# HighRangeAccelerometer.net
KiCad netlist of a schematic drawn in EAGLE
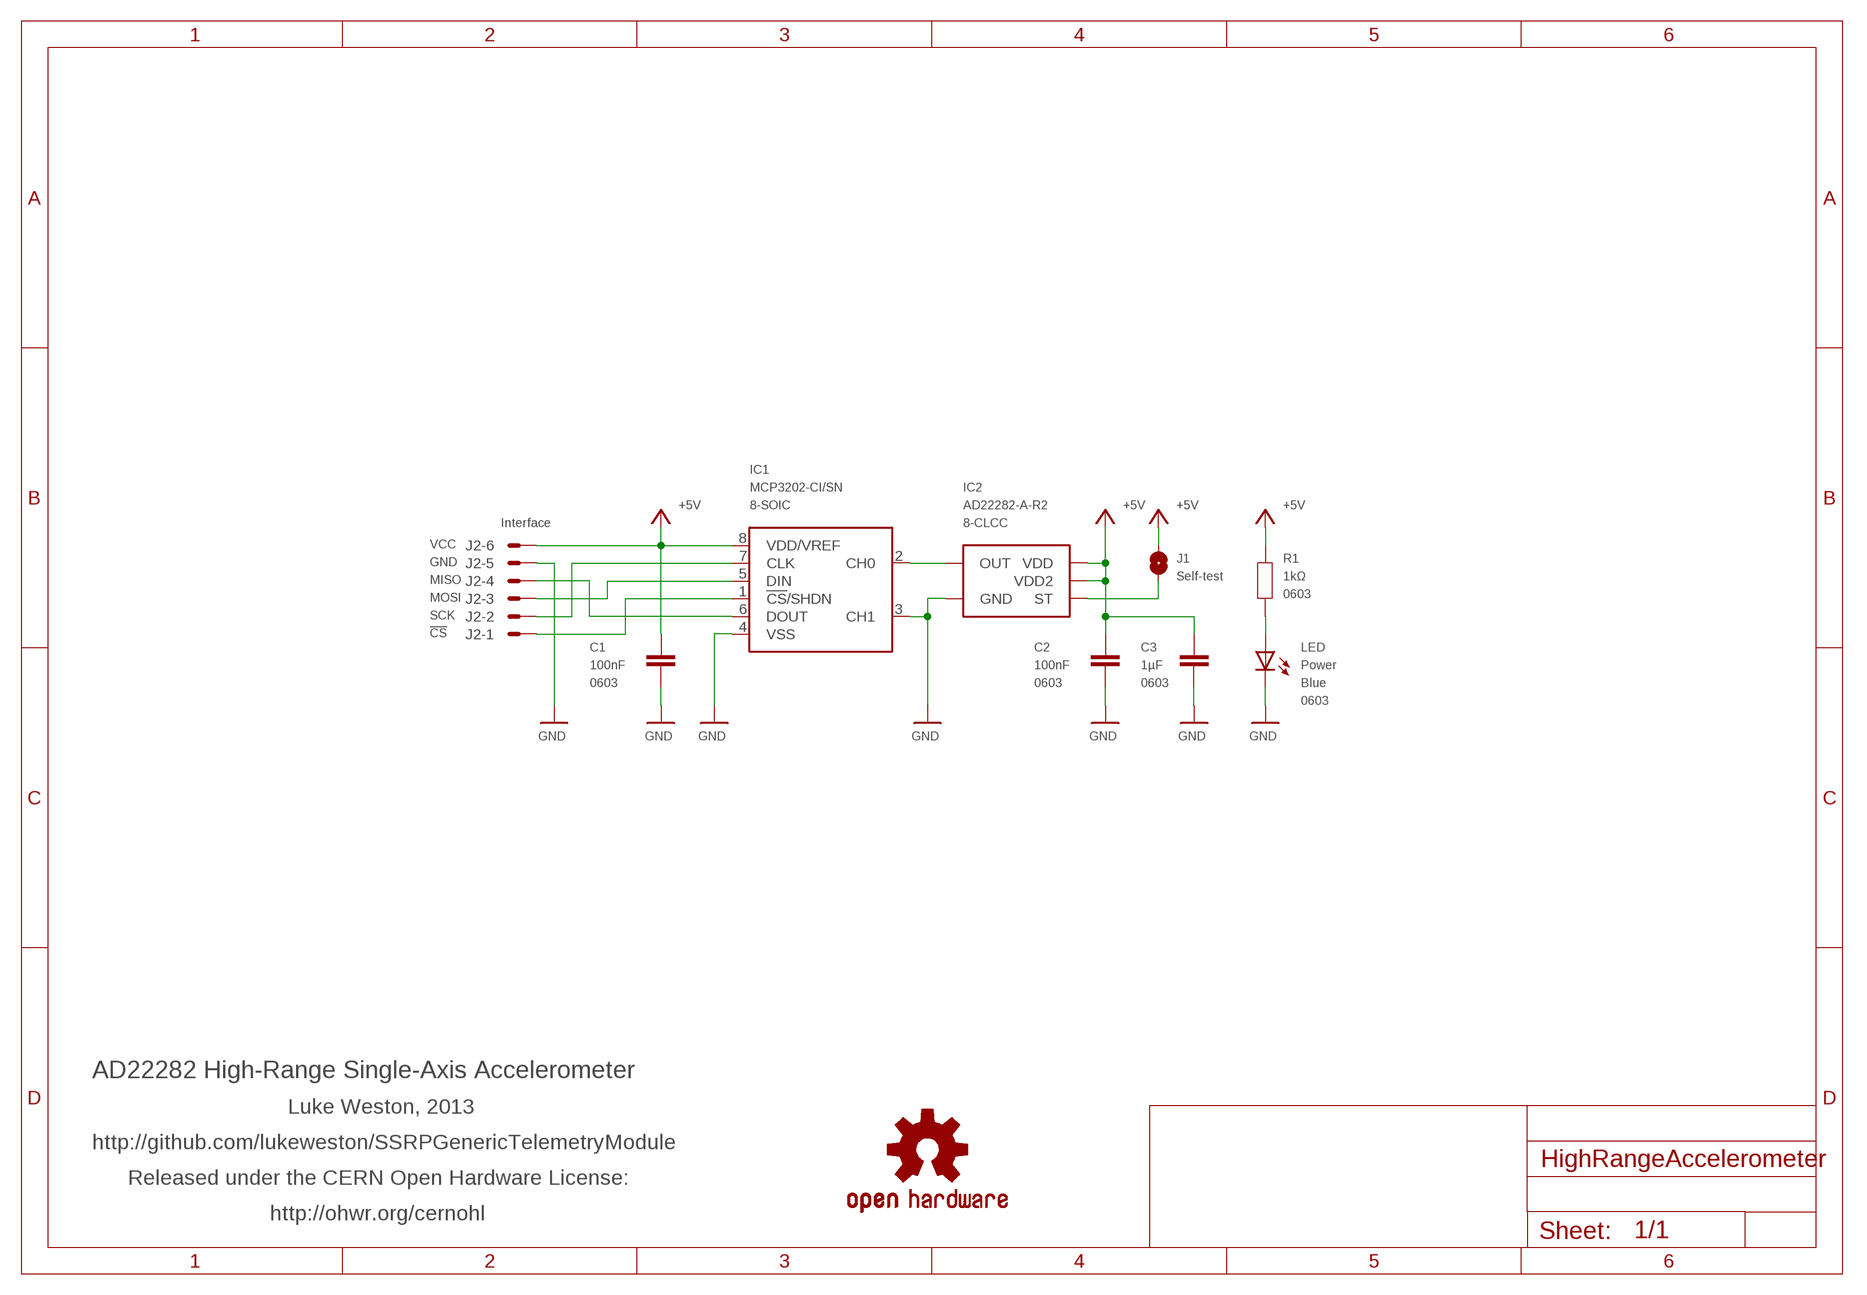
[diagram p0: schematic, sheet 1]

(export (version "E")
  (design (tool "Eeschema 10.0.6"))
  (components
    (comp (ref "C1")
      (value "100nF")
      (footprint "eagle-import:0603")
      (fields (field (name "PACKAGE") "0603"))
      (libsource (lib "eagle-import") (part "CAP0603"))
    )
    (comp (ref "C2")
      (value "100nF")
      (footprint "eagle-import:0603")
      (fields (field (name "PACKAGE") "0603"))
      (libsource (lib "eagle-import") (part "CAP0603"))
    )
    (comp (ref "C3")
      (value "1µF")
      (footprint "eagle-import:0603")
      (fields (field (name "PACKAGE") "0603"))
      (libsource (lib "eagle-import") (part "CAP0603"))
    )
    (comp (ref "IC1")
      (value "MCP3202-CI/SN")
      (footprint "eagle-import:SO-08")
      (fields (field (name "PACKAGE") "8-SOIC"))
      (libsource (lib "eagle-import") (part "MCP3202SN"))
    )
    (comp (ref "IC2")
      (value "AD22282-A-R2")
      (footprint "eagle-import:ADXL193")
      (fields (field (name "PACKAGE") "8-CLCC"))
      (libsource (lib "eagle-import") (part "ADXL193"))
    )
    (comp (ref "J1")
      (value "Self-test")
      (footprint "eagle-import:SJ")
      (libsource (lib "eagle-import") (part "SJ"))
    )
    (comp (ref "J2")
      (value "Interface")
      (footprint "eagle-import:22-23-2061")
      (fields (field (name "MF") "MOLEX") (field (name "MPN") "22-23-2061"))
      (libsource (lib "eagle-import") (part "22-23-2061"))
    )
    (comp (ref "LED")
      (value "Power")
      (footprint "eagle-import:LED-0603")
      (fields (field (name "COLOUR") "Blue") (field (name "PACKAGE") "0603"))
      (libsource (lib "eagle-import") (part "LED0603"))
    )
    (comp (ref "R1")
      (value "1kΩ")
      (footprint "eagle-import:0603")
      (fields (field (name "PACKAGE") "0603"))
      (libsource (lib "eagle-import") (part "RESISTOR0603"))
    )
    (comp (ref "SY")
      (value "OSHW-LOGOS")
      (footprint "eagle-import:OSHW-LOGO-S")
      (libsource (lib "eagle-import") (part "OSHW-LOGOS"))
    )
  )
  (nets
    (net (code "1") (name "+5V") (class "Default")
      (node (ref "C1") (pin "2") (pinfunction "2_2") (pintype "passive"))
      (node (ref "C2") (pin "2") (pinfunction "2_2") (pintype "passive"))
      (node (ref "C3") (pin "2") (pinfunction "2_2") (pintype "passive"))
      (node (ref "IC1") (pin "8") (pinfunction "VDD/VREF_8") (pintype "input"))
      (node (ref "IC2") (pin "P$7") (pinfunction "VDD_P$7") (pintype "bidirectional"))
      (node (ref "IC2") (pin "P$8") (pinfunction "VDD2_P$8") (pintype "bidirectional"))
      (node (ref "J1") (pin "2") (pinfunction "2_2") (pintype "passive"))
      (node (ref "J2") (pin "6") (pinfunction "S_6") (pintype "passive"))
      (node (ref "R1") (pin "2") (pinfunction "2_2") (pintype "passive"))
    )
    (net (code "2") (name "GND") (class "Default")
      (node (ref "C1") (pin "1") (pinfunction "1_1") (pintype "passive"))
      (node (ref "C2") (pin "1") (pinfunction "1_1") (pintype "passive"))
      (node (ref "C3") (pin "1") (pinfunction "1_1") (pintype "passive"))
      (node (ref "IC1") (pin "3") (pinfunction "CH1_3") (pintype "input"))
      (node (ref "IC1") (pin "4") (pinfunction "VSS_4") (pintype "input"))
      (node (ref "IC2") (pin "P$3") (pinfunction "GND_P$3") (pintype "bidirectional"))
      (node (ref "J2") (pin "5") (pinfunction "S_5") (pintype "passive"))
      (node (ref "LED") (pin "C") (pinfunction "C_C") (pintype "passive"))
    )
    (net (code "3") (name "Net-(IC1-CH0)") (class "Default")
      (node (ref "IC1") (pin "2") (pinfunction "CH0_2") (pintype "input"))
      (node (ref "IC2") (pin "P$6") (pinfunction "OUT_P$6") (pintype "bidirectional"))
    )
    (net (code "4") (name "Net-(IC1-CLK)") (class "Default")
      (node (ref "IC1") (pin "7") (pinfunction "CLK_7") (pintype "input"))
      (node (ref "J2") (pin "2") (pinfunction "S_2") (pintype "passive"))
    )
    (net (code "5") (name "Net-(IC1-DIN)") (class "Default")
      (node (ref "IC1") (pin "5") (pinfunction "DIN_5") (pintype "input"))
      (node (ref "J2") (pin "3") (pinfunction "S_3") (pintype "passive"))
    )
    (net (code "6") (name "Net-(IC1-DOUT)") (class "Default")
      (node (ref "IC1") (pin "6") (pinfunction "DOUT_6") (pintype "input"))
      (node (ref "J2") (pin "4") (pinfunction "S_4") (pintype "passive"))
    )
    (net (code "7") (name "Net-(IC1-~{CS}{slash}SHDN)") (class "Default")
      (node (ref "IC1") (pin "1") (pinfunction "~{CS}/SHDN_1") (pintype "input"))
      (node (ref "J2") (pin "1") (pinfunction "S_1") (pintype "passive"))
    )
    (net (code "8") (name "Net-(IC2-ST)") (class "Default")
      (node (ref "IC2") (pin "P$4") (pinfunction "ST_P$4") (pintype "bidirectional"))
      (node (ref "J1") (pin "1") (pinfunction "1_1") (pintype "passive"))
    )
    (net (code "9") (name "Net-(LED-PadA)") (class "Default")
      (node (ref "LED") (pin "A") (pinfunction "A_A") (pintype "passive"))
      (node (ref "R1") (pin "1") (pinfunction "1_1") (pintype "passive"))
    )
  )
)
